# cbjt-adc-demo.net
KiCad netlist of a schematic drawn in EAGLE
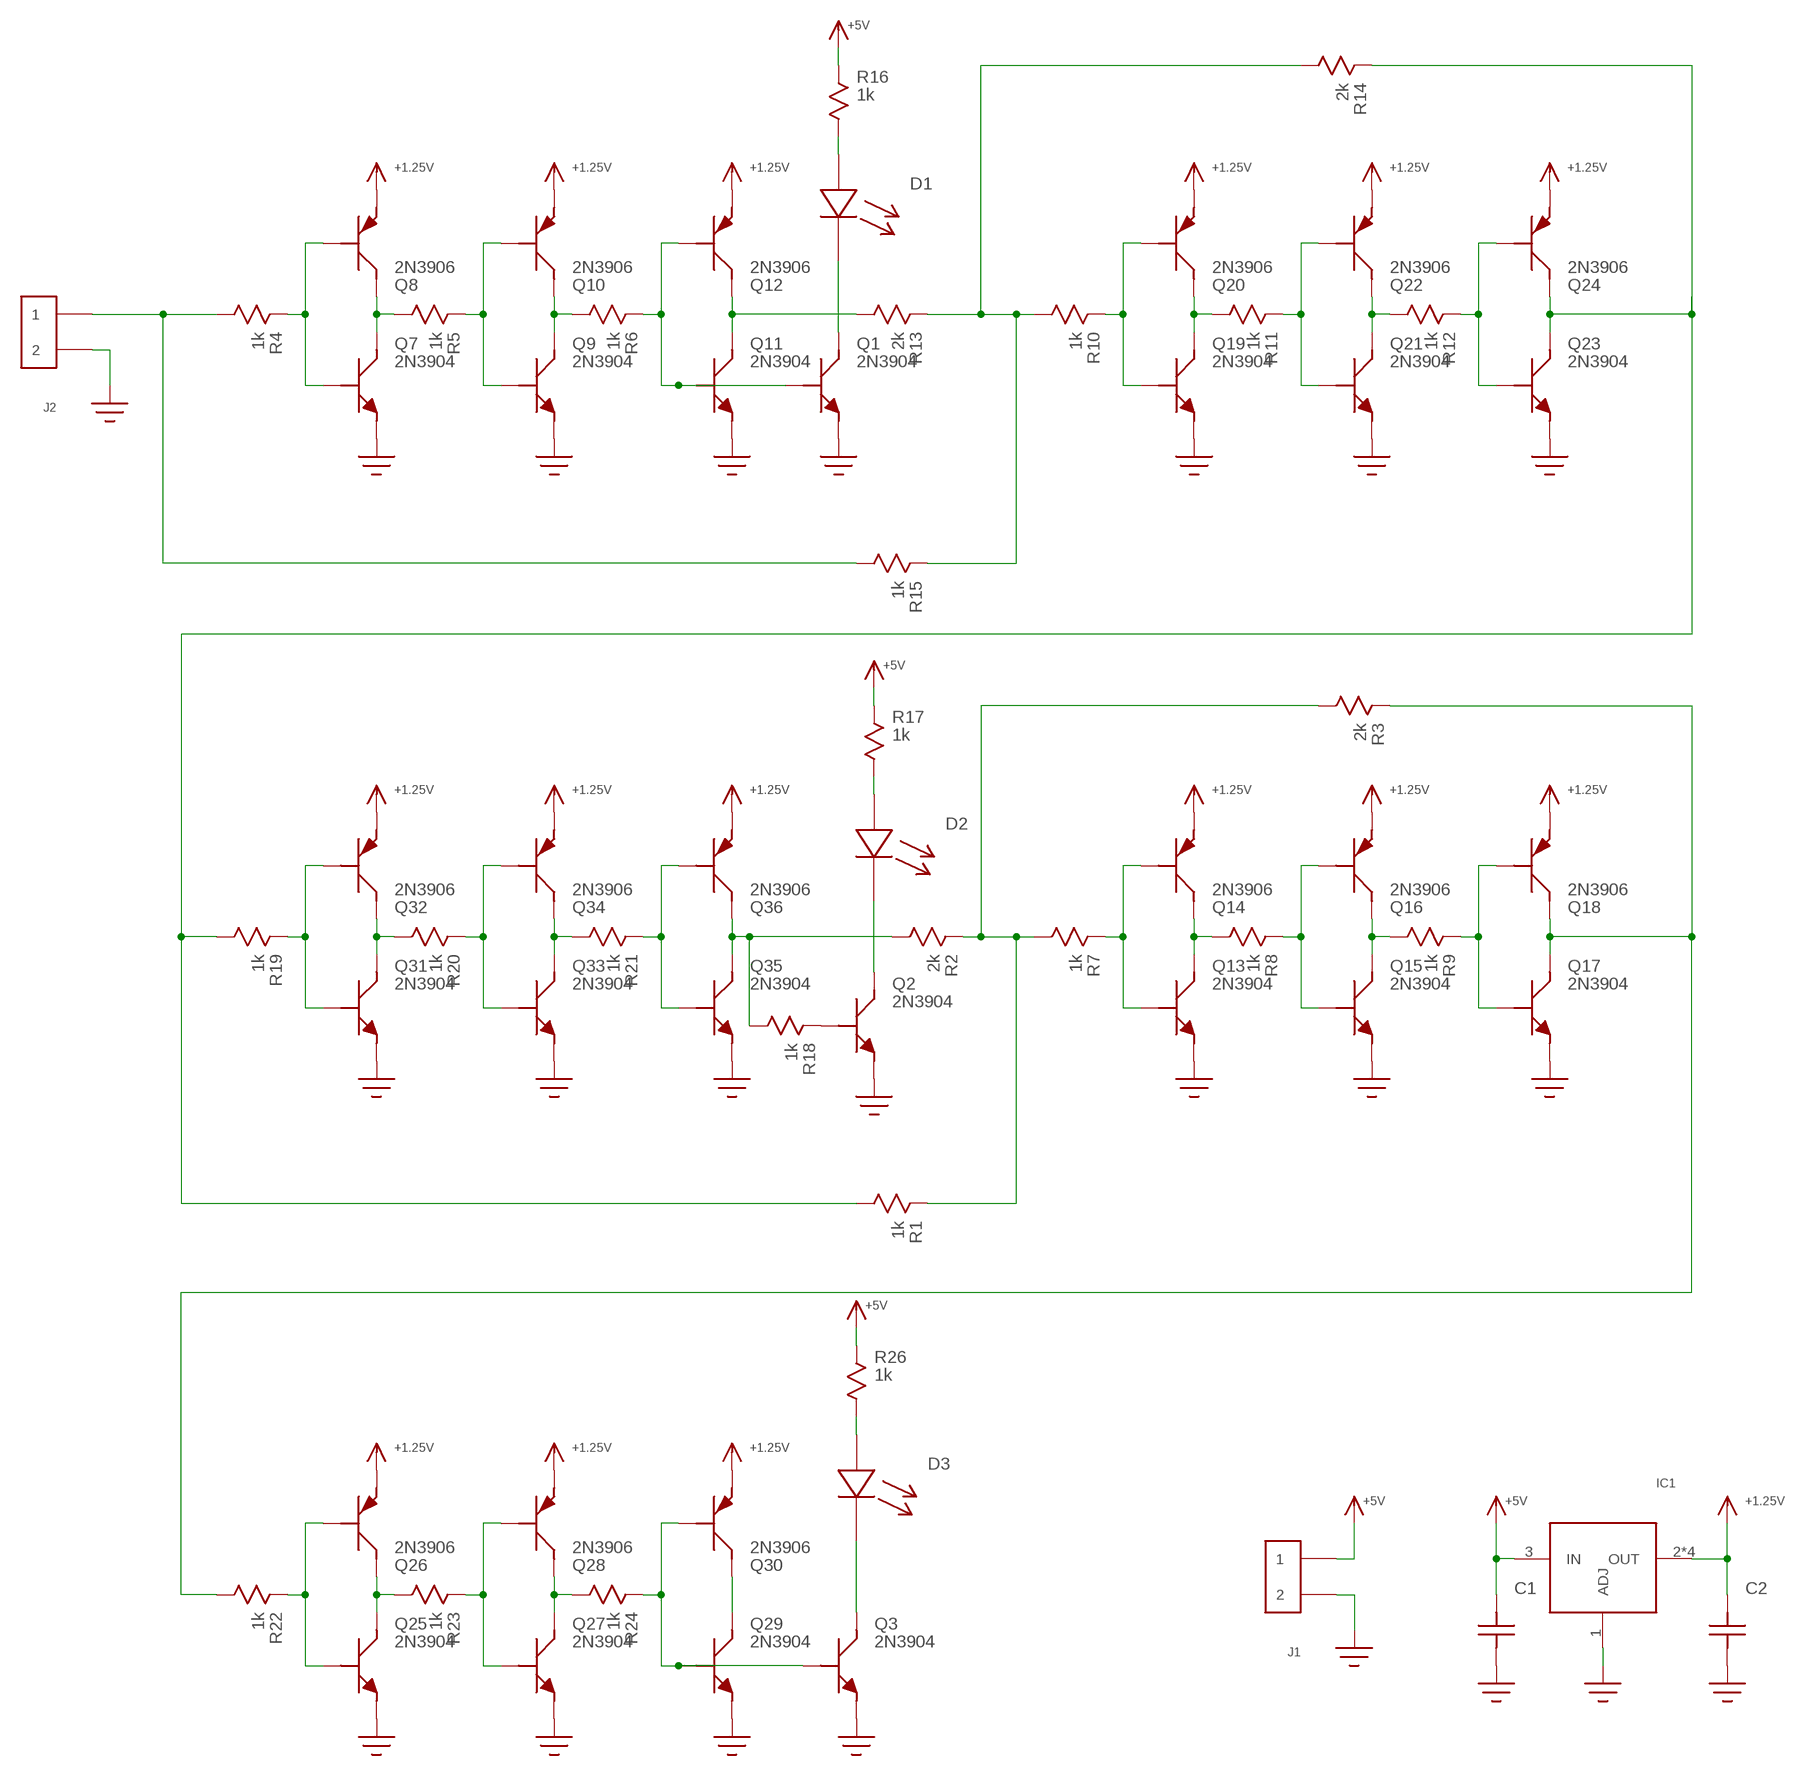
[diagram p0: schematic, sheet 1]

(export (version "E")
  (design (tool "Eeschema 10.0.6"))
  (components
    (comp (ref "C1")
      (value "C100MIL")
      (footprint "eagle-import:C-100MIL")
      (libsource (lib "eagle-import") (part "C100MIL"))
    )
    (comp (ref "C2")
      (value "C100MIL")
      (footprint "eagle-import:C-100MIL")
      (libsource (lib "eagle-import") (part "C100MIL"))
    )
    (comp (ref "D1")
      (value "LED5MM")
      (footprint "eagle-import:LED-5MM")
      (libsource (lib "eagle-import") (part "LED5MM"))
    )
    (comp (ref "D2")
      (value "LED5MM")
      (footprint "eagle-import:LED-5MM")
      (libsource (lib "eagle-import") (part "LED5MM"))
    )
    (comp (ref "D3")
      (value "LED5MM")
      (footprint "eagle-import:LED-5MM")
      (libsource (lib "eagle-import") (part "LED5MM"))
    )
    (comp (ref "IC1")
      (value "LM317")
      (footprint "eagle-import:TO-220")
      (libsource (lib "eagle-import") (part "LM317"))
    )
    (comp (ref "J1")
      (value "HEADER_2PIN")
      (footprint "eagle-import:HEADER_2PIN")
      (libsource (lib "eagle-import") (part "HEADER_2PIN"))
    )
    (comp (ref "J2")
      (value "HEADER_2PIN")
      (footprint "eagle-import:HEADER_2PIN")
      (libsource (lib "eagle-import") (part "HEADER_2PIN"))
    )
    (comp (ref "Q1")
      (value "2N3904")
      (footprint "eagle-import:TO-92")
      (libsource (lib "eagle-import") (part "NPNTO-92-EBC"))
    )
    (comp (ref "Q2")
      (value "2N3904")
      (footprint "eagle-import:TO-92")
      (libsource (lib "eagle-import") (part "NPNTO-92-EBC"))
    )
    (comp (ref "Q3")
      (value "2N3904")
      (footprint "eagle-import:TO-92")
      (libsource (lib "eagle-import") (part "NPNTO-92-EBC"))
    )
    (comp (ref "Q7")
      (value "2N3904")
      (footprint "eagle-import:TO-92")
      (libsource (lib "eagle-import") (part "NPNTO-92-EBC"))
    )
    (comp (ref "Q8")
      (value "2N3906")
      (footprint "eagle-import:TO-92")
      (libsource (lib "eagle-import") (part "PNPTO-92-EBC"))
    )
    (comp (ref "Q9")
      (value "2N3904")
      (footprint "eagle-import:TO-92")
      (libsource (lib "eagle-import") (part "NPNTO-92-EBC"))
    )
    (comp (ref "Q10")
      (value "2N3906")
      (footprint "eagle-import:TO-92")
      (libsource (lib "eagle-import") (part "PNPTO-92-EBC"))
    )
    (comp (ref "Q11")
      (value "2N3904")
      (footprint "eagle-import:TO-92")
      (libsource (lib "eagle-import") (part "NPNTO-92-EBC"))
    )
    (comp (ref "Q12")
      (value "2N3906")
      (footprint "eagle-import:TO-92")
      (libsource (lib "eagle-import") (part "PNPTO-92-EBC"))
    )
    (comp (ref "Q13")
      (value "2N3904")
      (footprint "eagle-import:TO-92")
      (libsource (lib "eagle-import") (part "NPNTO-92-EBC"))
    )
    (comp (ref "Q14")
      (value "2N3906")
      (footprint "eagle-import:TO-92")
      (libsource (lib "eagle-import") (part "PNPTO-92-EBC"))
    )
    (comp (ref "Q15")
      (value "2N3904")
      (footprint "eagle-import:TO-92")
      (libsource (lib "eagle-import") (part "NPNTO-92-EBC"))
    )
    (comp (ref "Q16")
      (value "2N3906")
      (footprint "eagle-import:TO-92")
      (libsource (lib "eagle-import") (part "PNPTO-92-EBC"))
    )
    (comp (ref "Q17")
      (value "2N3904")
      (footprint "eagle-import:TO-92")
      (libsource (lib "eagle-import") (part "NPNTO-92-EBC"))
    )
    (comp (ref "Q18")
      (value "2N3906")
      (footprint "eagle-import:TO-92")
      (libsource (lib "eagle-import") (part "PNPTO-92-EBC"))
    )
    (comp (ref "Q19")
      (value "2N3904")
      (footprint "eagle-import:TO-92")
      (libsource (lib "eagle-import") (part "NPNTO-92-EBC"))
    )
    (comp (ref "Q20")
      (value "2N3906")
      (footprint "eagle-import:TO-92")
      (libsource (lib "eagle-import") (part "PNPTO-92-EBC"))
    )
    (comp (ref "Q21")
      (value "2N3904")
      (footprint "eagle-import:TO-92")
      (libsource (lib "eagle-import") (part "NPNTO-92-EBC"))
    )
    (comp (ref "Q22")
      (value "2N3906")
      (footprint "eagle-import:TO-92")
      (libsource (lib "eagle-import") (part "PNPTO-92-EBC"))
    )
    (comp (ref "Q23")
      (value "2N3904")
      (footprint "eagle-import:TO-92")
      (libsource (lib "eagle-import") (part "NPNTO-92-EBC"))
    )
    (comp (ref "Q24")
      (value "2N3906")
      (footprint "eagle-import:TO-92")
      (libsource (lib "eagle-import") (part "PNPTO-92-EBC"))
    )
    (comp (ref "Q25")
      (value "2N3904")
      (footprint "eagle-import:TO-92")
      (libsource (lib "eagle-import") (part "NPNTO-92-EBC"))
    )
    (comp (ref "Q26")
      (value "2N3906")
      (footprint "eagle-import:TO-92")
      (libsource (lib "eagle-import") (part "PNPTO-92-EBC"))
    )
    (comp (ref "Q27")
      (value "2N3904")
      (footprint "eagle-import:TO-92")
      (libsource (lib "eagle-import") (part "NPNTO-92-EBC"))
    )
    (comp (ref "Q28")
      (value "2N3906")
      (footprint "eagle-import:TO-92")
      (libsource (lib "eagle-import") (part "PNPTO-92-EBC"))
    )
    (comp (ref "Q29")
      (value "2N3904")
      (footprint "eagle-import:TO-92")
      (libsource (lib "eagle-import") (part "NPNTO-92-EBC"))
    )
    (comp (ref "Q30")
      (value "2N3906")
      (footprint "eagle-import:TO-92")
      (libsource (lib "eagle-import") (part "PNPTO-92-EBC"))
    )
    (comp (ref "Q31")
      (value "2N3904")
      (footprint "eagle-import:TO-92")
      (libsource (lib "eagle-import") (part "NPNTO-92-EBC"))
    )
    (comp (ref "Q32")
      (value "2N3906")
      (footprint "eagle-import:TO-92")
      (libsource (lib "eagle-import") (part "PNPTO-92-EBC"))
    )
    (comp (ref "Q33")
      (value "2N3904")
      (footprint "eagle-import:TO-92")
      (libsource (lib "eagle-import") (part "NPNTO-92-EBC"))
    )
    (comp (ref "Q34")
      (value "2N3906")
      (footprint "eagle-import:TO-92")
      (libsource (lib "eagle-import") (part "PNPTO-92-EBC"))
    )
    (comp (ref "Q35")
      (value "2N3904")
      (footprint "eagle-import:TO-92")
      (libsource (lib "eagle-import") (part "NPNTO-92-EBC"))
    )
    (comp (ref "Q36")
      (value "2N3906")
      (footprint "eagle-import:TO-92")
      (libsource (lib "eagle-import") (part "PNPTO-92-EBC"))
    )
    (comp (ref "R1")
      (value "1k")
      (footprint "eagle-import:R-0.25W")
      (libsource (lib "eagle-import") (part "RTH-0.25W"))
    )
    (comp (ref "R2")
      (value "2k")
      (footprint "eagle-import:R-0.25W")
      (libsource (lib "eagle-import") (part "RTH-0.25W"))
    )
    (comp (ref "R3")
      (value "2k")
      (footprint "eagle-import:R-0.25W")
      (libsource (lib "eagle-import") (part "RTH-0.25W"))
    )
    (comp (ref "R4")
      (value "1k")
      (footprint "eagle-import:R-0.25W")
      (libsource (lib "eagle-import") (part "RTH-0.25W"))
    )
    (comp (ref "R5")
      (value "1k")
      (footprint "eagle-import:R-0.25W")
      (libsource (lib "eagle-import") (part "RTH-0.25W"))
    )
    (comp (ref "R6")
      (value "1k")
      (footprint "eagle-import:R-0.25W")
      (libsource (lib "eagle-import") (part "RTH-0.25W"))
    )
    (comp (ref "R7")
      (value "1k")
      (footprint "eagle-import:R-0.25W")
      (libsource (lib "eagle-import") (part "RTH-0.25W"))
    )
    (comp (ref "R8")
      (value "1k")
      (footprint "eagle-import:R-0.25W")
      (libsource (lib "eagle-import") (part "RTH-0.25W"))
    )
    (comp (ref "R9")
      (value "1k")
      (footprint "eagle-import:R-0.25W")
      (libsource (lib "eagle-import") (part "RTH-0.25W"))
    )
    (comp (ref "R10")
      (value "1k")
      (footprint "eagle-import:R-0.25W")
      (libsource (lib "eagle-import") (part "RTH-0.25W"))
    )
    (comp (ref "R11")
      (value "1k")
      (footprint "eagle-import:R-0.25W")
      (libsource (lib "eagle-import") (part "RTH-0.25W"))
    )
    (comp (ref "R12")
      (value "1k")
      (footprint "eagle-import:R-0.25W")
      (libsource (lib "eagle-import") (part "RTH-0.25W"))
    )
    (comp (ref "R13")
      (value "2k")
      (footprint "eagle-import:R-0.25W")
      (libsource (lib "eagle-import") (part "RTH-0.25W"))
    )
    (comp (ref "R14")
      (value "2k")
      (footprint "eagle-import:R-0.25W")
      (libsource (lib "eagle-import") (part "RTH-0.25W"))
    )
    (comp (ref "R15")
      (value "1k")
      (footprint "eagle-import:R-0.25W")
      (libsource (lib "eagle-import") (part "RTH-0.25W"))
    )
    (comp (ref "R16")
      (value "1k")
      (footprint "eagle-import:R-0.25W")
      (libsource (lib "eagle-import") (part "RTH-0.25W"))
    )
    (comp (ref "R17")
      (value "1k")
      (footprint "eagle-import:R-0.25W")
      (libsource (lib "eagle-import") (part "RTH-0.25W"))
    )
    (comp (ref "R18")
      (value "1k")
      (footprint "eagle-import:R-0.25W")
      (libsource (lib "eagle-import") (part "RTH-0.25W"))
    )
    (comp (ref "R19")
      (value "1k")
      (footprint "eagle-import:R-0.25W")
      (libsource (lib "eagle-import") (part "RTH-0.25W"))
    )
    (comp (ref "R20")
      (value "1k")
      (footprint "eagle-import:R-0.25W")
      (libsource (lib "eagle-import") (part "RTH-0.25W"))
    )
    (comp (ref "R21")
      (value "1k")
      (footprint "eagle-import:R-0.25W")
      (libsource (lib "eagle-import") (part "RTH-0.25W"))
    )
    (comp (ref "R22")
      (value "1k")
      (footprint "eagle-import:R-0.25W")
      (libsource (lib "eagle-import") (part "RTH-0.25W"))
    )
    (comp (ref "R23")
      (value "1k")
      (footprint "eagle-import:R-0.25W")
      (libsource (lib "eagle-import") (part "RTH-0.25W"))
    )
    (comp (ref "R24")
      (value "1k")
      (footprint "eagle-import:R-0.25W")
      (libsource (lib "eagle-import") (part "RTH-0.25W"))
    )
    (comp (ref "R26")
      (value "1k")
      (footprint "eagle-import:R-0.25W")
      (libsource (lib "eagle-import") (part "RTH-0.25W"))
    )
  )
  (nets
    (net (code "1") (name "+1.25V") (class "Default")
      (node (ref "C2") (pin "P$2") (pinfunction "P$2_P$2") (pintype "bidirectional"))
      (node (ref "IC1") (pin "2") (pinfunction "OUT_2") (pintype "bidirectional"))
      (node (ref "IC1") (pin "HS@1") (pinfunction "OUT_HS@1") (pintype "bidirectional"))
      (node (ref "IC1") (pin "HS@2") (pinfunction "OUT_HS@2") (pintype "bidirectional"))
      (node (ref "IC1") (pin "HS@3") (pinfunction "OUT_HS@3") (pintype "bidirectional"))
      (node (ref "Q10") (pin "1") (pinfunction "E_1") (pintype "bidirectional"))
      (node (ref "Q12") (pin "1") (pinfunction "E_1") (pintype "bidirectional"))
      (node (ref "Q14") (pin "1") (pinfunction "E_1") (pintype "bidirectional"))
      (node (ref "Q16") (pin "1") (pinfunction "E_1") (pintype "bidirectional"))
      (node (ref "Q18") (pin "1") (pinfunction "E_1") (pintype "bidirectional"))
      (node (ref "Q20") (pin "1") (pinfunction "E_1") (pintype "bidirectional"))
      (node (ref "Q22") (pin "1") (pinfunction "E_1") (pintype "bidirectional"))
      (node (ref "Q24") (pin "1") (pinfunction "E_1") (pintype "bidirectional"))
      (node (ref "Q26") (pin "1") (pinfunction "E_1") (pintype "bidirectional"))
      (node (ref "Q28") (pin "1") (pinfunction "E_1") (pintype "bidirectional"))
      (node (ref "Q30") (pin "1") (pinfunction "E_1") (pintype "bidirectional"))
      (node (ref "Q32") (pin "1") (pinfunction "E_1") (pintype "bidirectional"))
      (node (ref "Q34") (pin "1") (pinfunction "E_1") (pintype "bidirectional"))
      (node (ref "Q36") (pin "1") (pinfunction "E_1") (pintype "bidirectional"))
      (node (ref "Q8") (pin "1") (pinfunction "E_1") (pintype "bidirectional"))
    )
    (net (code "2") (name "+5V") (class "Default")
      (node (ref "C1") (pin "P$2") (pinfunction "P$2_P$2") (pintype "bidirectional"))
      (node (ref "IC1") (pin "3") (pinfunction "IN_3") (pintype "bidirectional"))
      (node (ref "J1") (pin "1") (pinfunction "1_1") (pintype "bidirectional"))
      (node (ref "R16") (pin "P$1") (pinfunction "P$3_P$1") (pintype "bidirectional"))
      (node (ref "R17") (pin "P$1") (pinfunction "P$3_P$1") (pintype "bidirectional"))
      (node (ref "R26") (pin "P$1") (pinfunction "P$3_P$1") (pintype "bidirectional"))
    )
    (net (code "3") (name "GND") (class "Default")
      (node (ref "C1") (pin "P$1") (pinfunction "P$1_P$1") (pintype "bidirectional"))
      (node (ref "C2") (pin "P$1") (pinfunction "P$1_P$1") (pintype "bidirectional"))
      (node (ref "IC1") (pin "1") (pinfunction "ADJ_1") (pintype "bidirectional"))
      (node (ref "J1") (pin "2") (pinfunction "2_2") (pintype "bidirectional"))
      (node (ref "J2") (pin "2") (pinfunction "2_2") (pintype "bidirectional"))
      (node (ref "Q1") (pin "1") (pinfunction "E_1") (pintype "bidirectional"))
      (node (ref "Q11") (pin "1") (pinfunction "E_1") (pintype "bidirectional"))
      (node (ref "Q13") (pin "1") (pinfunction "E_1") (pintype "bidirectional"))
      (node (ref "Q15") (pin "1") (pinfunction "E_1") (pintype "bidirectional"))
      (node (ref "Q17") (pin "1") (pinfunction "E_1") (pintype "bidirectional"))
      (node (ref "Q19") (pin "1") (pinfunction "E_1") (pintype "bidirectional"))
      (node (ref "Q2") (pin "1") (pinfunction "E_1") (pintype "bidirectional"))
      (node (ref "Q21") (pin "1") (pinfunction "E_1") (pintype "bidirectional"))
      (node (ref "Q23") (pin "1") (pinfunction "E_1") (pintype "bidirectional"))
      (node (ref "Q25") (pin "1") (pinfunction "E_1") (pintype "bidirectional"))
      (node (ref "Q27") (pin "1") (pinfunction "E_1") (pintype "bidirectional"))
      (node (ref "Q29") (pin "1") (pinfunction "E_1") (pintype "bidirectional"))
      (node (ref "Q3") (pin "1") (pinfunction "E_1") (pintype "bidirectional"))
      (node (ref "Q31") (pin "1") (pinfunction "E_1") (pintype "bidirectional"))
      (node (ref "Q33") (pin "1") (pinfunction "E_1") (pintype "bidirectional"))
      (node (ref "Q35") (pin "1") (pinfunction "E_1") (pintype "bidirectional"))
      (node (ref "Q7") (pin "1") (pinfunction "E_1") (pintype "bidirectional"))
      (node (ref "Q9") (pin "1") (pinfunction "E_1") (pintype "bidirectional"))
    )
    (net (code "4") (name "Net-(Q1-B)") (class "Default")
      (node (ref "Q1") (pin "2") (pinfunction "B_2") (pintype "bidirectional"))
      (node (ref "Q11") (pin "2") (pinfunction "B_2") (pintype "bidirectional"))
      (node (ref "Q12") (pin "2") (pinfunction "B_2") (pintype "bidirectional"))
      (node (ref "R6") (pin "P$1") (pinfunction "P$3_P$1") (pintype "bidirectional"))
    )
    (net (code "5") (name "Net-(Q1-C)") (class "Default")
      (node (ref "D1") (pin "C") (pinfunction "C_C") (pintype "bidirectional"))
      (node (ref "Q1") (pin "3") (pinfunction "C_3") (pintype "bidirectional"))
    )
    (net (code "6") (name "Net-(Q2-B)") (class "Default")
      (node (ref "Q2") (pin "2") (pinfunction "B_2") (pintype "bidirectional"))
      (node (ref "R18") (pin "P$1") (pinfunction "P$3_P$1") (pintype "bidirectional"))
    )
    (net (code "7") (name "Net-(Q2-C)") (class "Default")
      (node (ref "D2") (pin "C") (pinfunction "C_C") (pintype "bidirectional"))
      (node (ref "Q2") (pin "3") (pinfunction "C_3") (pintype "bidirectional"))
    )
    (net (code "8") (name "Net-(Q3-C)") (class "Default")
      (node (ref "D3") (pin "C") (pinfunction "C_C") (pintype "bidirectional"))
      (node (ref "Q3") (pin "3") (pinfunction "C_3") (pintype "bidirectional"))
    )
    (net (code "9") (name "Net-(Q7-B)") (class "Default")
      (node (ref "Q7") (pin "2") (pinfunction "B_2") (pintype "bidirectional"))
      (node (ref "Q8") (pin "2") (pinfunction "B_2") (pintype "bidirectional"))
      (node (ref "R4") (pin "P$1") (pinfunction "P$3_P$1") (pintype "bidirectional"))
    )
    (net (code "10") (name "Net-(Q7-C)") (class "Default")
      (node (ref "Q7") (pin "3") (pinfunction "C_3") (pintype "bidirectional"))
      (node (ref "Q8") (pin "3") (pinfunction "C_3") (pintype "bidirectional"))
      (node (ref "R5") (pin "P$2") (pinfunction "P$4_P$2") (pintype "bidirectional"))
    )
    (net (code "11") (name "Net-(Q10-B)") (class "Default")
      (node (ref "Q10") (pin "2") (pinfunction "B_2") (pintype "bidirectional"))
      (node (ref "Q9") (pin "2") (pinfunction "B_2") (pintype "bidirectional"))
      (node (ref "R5") (pin "P$1") (pinfunction "P$3_P$1") (pintype "bidirectional"))
    )
    (net (code "12") (name "Net-(Q10-C)") (class "Default")
      (node (ref "Q10") (pin "3") (pinfunction "C_3") (pintype "bidirectional"))
      (node (ref "Q9") (pin "3") (pinfunction "C_3") (pintype "bidirectional"))
      (node (ref "R6") (pin "P$2") (pinfunction "P$4_P$2") (pintype "bidirectional"))
    )
    (net (code "13") (name "Net-(Q11-C)") (class "Default")
      (node (ref "Q11") (pin "3") (pinfunction "C_3") (pintype "bidirectional"))
      (node (ref "Q12") (pin "3") (pinfunction "C_3") (pintype "bidirectional"))
      (node (ref "R13") (pin "P$2") (pinfunction "P$4_P$2") (pintype "bidirectional"))
    )
    (net (code "14") (name "Net-(Q13-B)") (class "Default")
      (node (ref "Q13") (pin "2") (pinfunction "B_2") (pintype "bidirectional"))
      (node (ref "Q14") (pin "2") (pinfunction "B_2") (pintype "bidirectional"))
      (node (ref "R7") (pin "P$1") (pinfunction "P$3_P$1") (pintype "bidirectional"))
    )
    (net (code "15") (name "Net-(Q13-C)") (class "Default")
      (node (ref "Q13") (pin "3") (pinfunction "C_3") (pintype "bidirectional"))
      (node (ref "Q14") (pin "3") (pinfunction "C_3") (pintype "bidirectional"))
      (node (ref "R8") (pin "P$2") (pinfunction "P$4_P$2") (pintype "bidirectional"))
    )
    (net (code "16") (name "Net-(Q15-B)") (class "Default")
      (node (ref "Q15") (pin "2") (pinfunction "B_2") (pintype "bidirectional"))
      (node (ref "Q16") (pin "2") (pinfunction "B_2") (pintype "bidirectional"))
      (node (ref "R8") (pin "P$1") (pinfunction "P$3_P$1") (pintype "bidirectional"))
    )
    (net (code "17") (name "Net-(Q15-C)") (class "Default")
      (node (ref "Q15") (pin "3") (pinfunction "C_3") (pintype "bidirectional"))
      (node (ref "Q16") (pin "3") (pinfunction "C_3") (pintype "bidirectional"))
      (node (ref "R9") (pin "P$2") (pinfunction "P$4_P$2") (pintype "bidirectional"))
    )
    (net (code "18") (name "Net-(Q17-B)") (class "Default")
      (node (ref "Q17") (pin "2") (pinfunction "B_2") (pintype "bidirectional"))
      (node (ref "Q18") (pin "2") (pinfunction "B_2") (pintype "bidirectional"))
      (node (ref "R9") (pin "P$1") (pinfunction "P$3_P$1") (pintype "bidirectional"))
    )
    (net (code "19") (name "Net-(Q17-C)") (class "Default")
      (node (ref "Q17") (pin "3") (pinfunction "C_3") (pintype "bidirectional"))
      (node (ref "Q18") (pin "3") (pinfunction "C_3") (pintype "bidirectional"))
      (node (ref "R22") (pin "P$2") (pinfunction "P$4_P$2") (pintype "bidirectional"))
      (node (ref "R3") (pin "P$1") (pinfunction "P$3_P$1") (pintype "bidirectional"))
    )
    (net (code "20") (name "Net-(Q19-B)") (class "Default")
      (node (ref "Q19") (pin "2") (pinfunction "B_2") (pintype "bidirectional"))
      (node (ref "Q20") (pin "2") (pinfunction "B_2") (pintype "bidirectional"))
      (node (ref "R10") (pin "P$1") (pinfunction "P$3_P$1") (pintype "bidirectional"))
    )
    (net (code "21") (name "Net-(Q19-C)") (class "Default")
      (node (ref "Q19") (pin "3") (pinfunction "C_3") (pintype "bidirectional"))
      (node (ref "Q20") (pin "3") (pinfunction "C_3") (pintype "bidirectional"))
      (node (ref "R11") (pin "P$2") (pinfunction "P$4_P$2") (pintype "bidirectional"))
    )
    (net (code "22") (name "Net-(Q21-B)") (class "Default")
      (node (ref "Q21") (pin "2") (pinfunction "B_2") (pintype "bidirectional"))
      (node (ref "Q22") (pin "2") (pinfunction "B_2") (pintype "bidirectional"))
      (node (ref "R11") (pin "P$1") (pinfunction "P$3_P$1") (pintype "bidirectional"))
    )
    (net (code "23") (name "Net-(Q21-C)") (class "Default")
      (node (ref "Q21") (pin "3") (pinfunction "C_3") (pintype "bidirectional"))
      (node (ref "Q22") (pin "3") (pinfunction "C_3") (pintype "bidirectional"))
      (node (ref "R12") (pin "P$2") (pinfunction "P$4_P$2") (pintype "bidirectional"))
    )
    (net (code "24") (name "Net-(Q23-B)") (class "Default")
      (node (ref "Q23") (pin "2") (pinfunction "B_2") (pintype "bidirectional"))
      (node (ref "Q24") (pin "2") (pinfunction "B_2") (pintype "bidirectional"))
      (node (ref "R12") (pin "P$1") (pinfunction "P$3_P$1") (pintype "bidirectional"))
    )
    (net (code "25") (name "Net-(Q23-C)") (class "Default")
      (node (ref "Q23") (pin "3") (pinfunction "C_3") (pintype "bidirectional"))
      (node (ref "Q24") (pin "3") (pinfunction "C_3") (pintype "bidirectional"))
      (node (ref "R1") (pin "P$2") (pinfunction "P$4_P$2") (pintype "bidirectional"))
      (node (ref "R14") (pin "P$1") (pinfunction "P$3_P$1") (pintype "bidirectional"))
      (node (ref "R19") (pin "P$2") (pinfunction "P$4_P$2") (pintype "bidirectional"))
    )
    (net (code "26") (name "Net-(Q25-B)") (class "Default")
      (node (ref "Q25") (pin "2") (pinfunction "B_2") (pintype "bidirectional"))
      (node (ref "Q26") (pin "2") (pinfunction "B_2") (pintype "bidirectional"))
      (node (ref "R22") (pin "P$1") (pinfunction "P$3_P$1") (pintype "bidirectional"))
    )
    (net (code "27") (name "Net-(Q25-C)") (class "Default")
      (node (ref "Q25") (pin "3") (pinfunction "C_3") (pintype "bidirectional"))
      (node (ref "Q26") (pin "3") (pinfunction "C_3") (pintype "bidirectional"))
      (node (ref "R23") (pin "P$2") (pinfunction "P$4_P$2") (pintype "bidirectional"))
    )
    (net (code "28") (name "Net-(Q27-B)") (class "Default")
      (node (ref "Q27") (pin "2") (pinfunction "B_2") (pintype "bidirectional"))
      (node (ref "Q28") (pin "2") (pinfunction "B_2") (pintype "bidirectional"))
      (node (ref "R23") (pin "P$1") (pinfunction "P$3_P$1") (pintype "bidirectional"))
    )
    (net (code "29") (name "Net-(Q27-C)") (class "Default")
      (node (ref "Q27") (pin "3") (pinfunction "C_3") (pintype "bidirectional"))
      (node (ref "Q28") (pin "3") (pinfunction "C_3") (pintype "bidirectional"))
      (node (ref "R24") (pin "P$2") (pinfunction "P$4_P$2") (pintype "bidirectional"))
    )
    (net (code "30") (name "Net-(Q29-B)") (class "Default")
      (node (ref "Q29") (pin "2") (pinfunction "B_2") (pintype "bidirectional"))
      (node (ref "Q3") (pin "2") (pinfunction "B_2") (pintype "bidirectional"))
      (node (ref "Q30") (pin "2") (pinfunction "B_2") (pintype "bidirectional"))
      (node (ref "R24") (pin "P$1") (pinfunction "P$3_P$1") (pintype "bidirectional"))
    )
    (net (code "31") (name "Net-(Q29-C)") (class "Default")
      (node (ref "Q29") (pin "3") (pinfunction "C_3") (pintype "bidirectional"))
      (node (ref "Q30") (pin "3") (pinfunction "C_3") (pintype "bidirectional"))
    )
    (net (code "32") (name "Net-(Q31-B)") (class "Default")
      (node (ref "Q31") (pin "2") (pinfunction "B_2") (pintype "bidirectional"))
      (node (ref "Q32") (pin "2") (pinfunction "B_2") (pintype "bidirectional"))
      (node (ref "R19") (pin "P$1") (pinfunction "P$3_P$1") (pintype "bidirectional"))
    )
    (net (code "33") (name "Net-(Q31-C)") (class "Default")
      (node (ref "Q31") (pin "3") (pinfunction "C_3") (pintype "bidirectional"))
      (node (ref "Q32") (pin "3") (pinfunction "C_3") (pintype "bidirectional"))
      (node (ref "R20") (pin "P$2") (pinfunction "P$4_P$2") (pintype "bidirectional"))
    )
    (net (code "34") (name "Net-(Q33-B)") (class "Default")
      (node (ref "Q33") (pin "2") (pinfunction "B_2") (pintype "bidirectional"))
      (node (ref "Q34") (pin "2") (pinfunction "B_2") (pintype "bidirectional"))
      (node (ref "R20") (pin "P$1") (pinfunction "P$3_P$1") (pintype "bidirectional"))
    )
    (net (code "35") (name "Net-(Q33-C)") (class "Default")
      (node (ref "Q33") (pin "3") (pinfunction "C_3") (pintype "bidirectional"))
      (node (ref "Q34") (pin "3") (pinfunction "C_3") (pintype "bidirectional"))
      (node (ref "R21") (pin "P$2") (pinfunction "P$4_P$2") (pintype "bidirectional"))
    )
    (net (code "36") (name "Net-(Q35-B)") (class "Default")
      (node (ref "Q35") (pin "2") (pinfunction "B_2") (pintype "bidirectional"))
      (node (ref "Q36") (pin "2") (pinfunction "B_2") (pintype "bidirectional"))
      (node (ref "R21") (pin "P$1") (pinfunction "P$3_P$1") (pintype "bidirectional"))
    )
    (net (code "37") (name "Net-(Q35-C)") (class "Default")
      (node (ref "Q35") (pin "3") (pinfunction "C_3") (pintype "bidirectional"))
      (node (ref "Q36") (pin "3") (pinfunction "C_3") (pintype "bidirectional"))
      (node (ref "R18") (pin "P$2") (pinfunction "P$4_P$2") (pintype "bidirectional"))
      (node (ref "R2") (pin "P$2") (pinfunction "P$4_P$2") (pintype "bidirectional"))
    )
    (net (code "38") (name "Net-(R1-P$3)") (class "Default")
      (node (ref "R1") (pin "P$1") (pinfunction "P$3_P$1") (pintype "bidirectional"))
      (node (ref "R2") (pin "P$1") (pinfunction "P$3_P$1") (pintype "bidirectional"))
      (node (ref "R3") (pin "P$2") (pinfunction "P$4_P$2") (pintype "bidirectional"))
      (node (ref "R7") (pin "P$2") (pinfunction "P$4_P$2") (pintype "bidirectional"))
    )
    (net (code "39") (name "Net-(R10-P$4)") (class "Default")
      (node (ref "R10") (pin "P$2") (pinfunction "P$4_P$2") (pintype "bidirectional"))
      (node (ref "R13") (pin "P$1") (pinfunction "P$3_P$1") (pintype "bidirectional"))
      (node (ref "R14") (pin "P$2") (pinfunction "P$4_P$2") (pintype "bidirectional"))
      (node (ref "R15") (pin "P$1") (pinfunction "P$3_P$1") (pintype "bidirectional"))
    )
    (net (code "40") (name "Net-(R15-P$4)") (class "Default")
      (node (ref "J2") (pin "1") (pinfunction "1_1") (pintype "bidirectional"))
      (node (ref "R15") (pin "P$2") (pinfunction "P$4_P$2") (pintype "bidirectional"))
      (node (ref "R4") (pin "P$2") (pinfunction "P$4_P$2") (pintype "bidirectional"))
    )
    (net (code "41") (name "Net-(R16-P$4)") (class "Default")
      (node (ref "D1") (pin "A") (pinfunction "A_A") (pintype "bidirectional"))
      (node (ref "R16") (pin "P$2") (pinfunction "P$4_P$2") (pintype "bidirectional"))
    )
    (net (code "42") (name "Net-(R17-P$4)") (class "Default")
      (node (ref "D2") (pin "A") (pinfunction "A_A") (pintype "bidirectional"))
      (node (ref "R17") (pin "P$2") (pinfunction "P$4_P$2") (pintype "bidirectional"))
    )
    (net (code "43") (name "Net-(R26-P$4)") (class "Default")
      (node (ref "D3") (pin "A") (pinfunction "A_A") (pintype "bidirectional"))
      (node (ref "R26") (pin "P$2") (pinfunction "P$4_P$2") (pintype "bidirectional"))
    )
  )
)
